# Power.net
KiCad netlist of a schematic drawn in Altium Designer
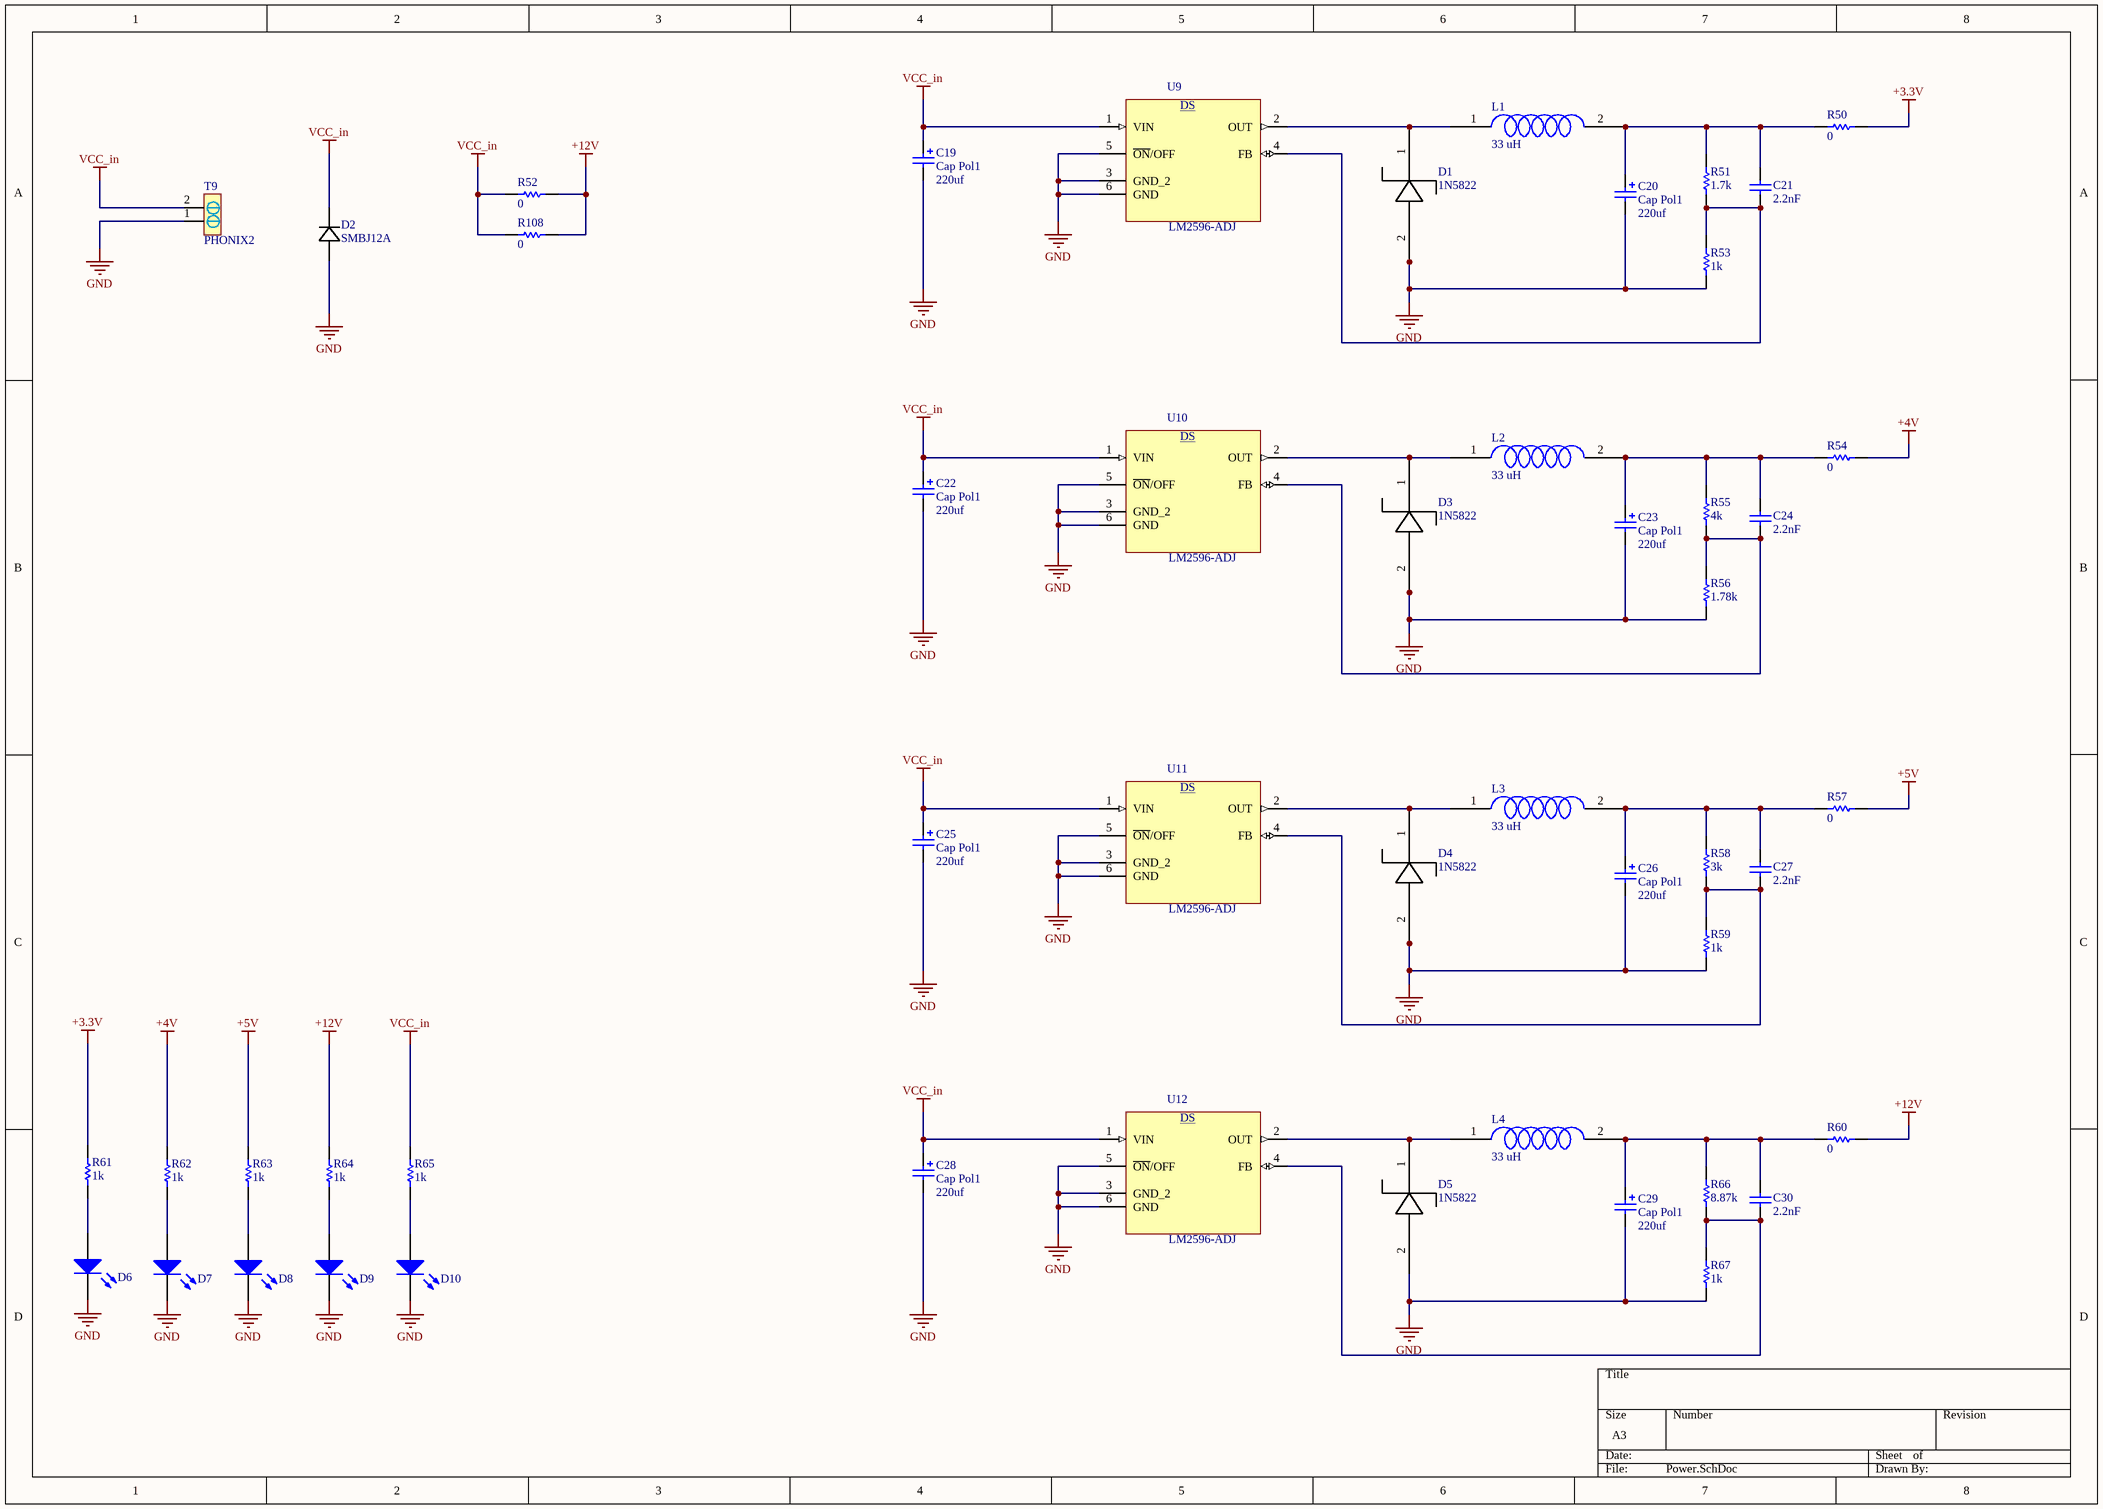
[diagram p0: Power.SchDoc]

(export (version "E")
  (design (tool "Eeschema 10.0.6"))
  (components
    (comp (ref "C19")
      (value "Cap Pol1")
      (footprint "RB5-10.5")
      (description "Polarized Capacitor (Radial)")
      (fields (field (name "ALTIUM_VALUE") "220uf") (field (name "PUBLISHER") "Altium Limited"))
      (libsource (lib "AfraLIB") (part "Cap Pol1"))
    )
    (comp (ref "C20")
      (value "Cap Pol1")
      (footprint "RB5-10.5")
      (description "Polarized Capacitor (Radial)")
      (fields (field (name "ALTIUM_VALUE") "220uf") (field (name "PUBLISHER") "Altium Limited"))
      (libsource (lib "AfraLIB") (part "Cap Pol1"))
    )
    (comp (ref "C21")
      (value "2.2nF")
      (footprint "C-805")
      (description "Capacitor")
      (fields (field (name "Comment") "C-805") (field (name "PUBLISHER") "Altium Limited"))
      (libsource (lib "AfraLIB") (part "C-805"))
    )
    (comp (ref "C22")
      (value "Cap Pol1")
      (footprint "RB5-10.5")
      (description "Polarized Capacitor (Radial)")
      (fields (field (name "ALTIUM_VALUE") "220uf") (field (name "PUBLISHER") "Altium Limited"))
      (libsource (lib "AfraLIB") (part "Cap Pol1"))
    )
    (comp (ref "C23")
      (value "Cap Pol1")
      (footprint "RB5-10.5")
      (description "Polarized Capacitor (Radial)")
      (fields (field (name "ALTIUM_VALUE") "220uf") (field (name "PUBLISHER") "Altium Limited"))
      (libsource (lib "AfraLIB") (part "Cap Pol1"))
    )
    (comp (ref "C24")
      (value "2.2nF")
      (footprint "C-805")
      (description "Capacitor")
      (fields (field (name "Comment") "C-805") (field (name "PUBLISHER") "Altium Limited"))
      (libsource (lib "AfraLIB") (part "C-805"))
    )
    (comp (ref "C25")
      (value "Cap Pol1")
      (footprint "RB5-10.5")
      (description "Polarized Capacitor (Radial)")
      (fields (field (name "ALTIUM_VALUE") "220uf") (field (name "PUBLISHER") "Altium Limited"))
      (libsource (lib "AfraLIB") (part "Cap Pol1"))
    )
    (comp (ref "C26")
      (value "Cap Pol1")
      (footprint "RB5-10.5")
      (description "Polarized Capacitor (Radial)")
      (fields (field (name "ALTIUM_VALUE") "220uf") (field (name "PUBLISHER") "Altium Limited"))
      (libsource (lib "AfraLIB") (part "Cap Pol1"))
    )
    (comp (ref "C27")
      (value "2.2nF")
      (footprint "C-805")
      (description "Capacitor")
      (fields (field (name "Comment") "C-805") (field (name "PUBLISHER") "Altium Limited"))
      (libsource (lib "AfraLIB") (part "C-805"))
    )
    (comp (ref "C28")
      (value "Cap Pol1")
      (footprint "RB5-10.5")
      (description "Polarized Capacitor (Radial)")
      (fields (field (name "ALTIUM_VALUE") "220uf") (field (name "PUBLISHER") "Altium Limited"))
      (libsource (lib "AfraLIB") (part "Cap Pol1"))
    )
    (comp (ref "C29")
      (value "Cap Pol1")
      (footprint "RB5-10.5")
      (description "Polarized Capacitor (Radial)")
      (fields (field (name "ALTIUM_VALUE") "220uf") (field (name "PUBLISHER") "Altium Limited"))
      (libsource (lib "AfraLIB") (part "Cap Pol1"))
    )
    (comp (ref "C30")
      (value "2.2nF")
      (footprint "C-805")
      (description "Capacitor")
      (fields (field (name "Comment") "C-805") (field (name "PUBLISHER") "Altium Limited"))
      (libsource (lib "AfraLIB") (part "C-805"))
    )
    (comp (ref "D1") (value "1N5822") (footprint "1N5822") (libsource (lib "AfraLIB") (part "1N5822")))
    (comp (ref "D2")
      (value "SMBJ12A")
      (footprint "SMB")
      (description "No Description Available")
      (fields
        (field (name "MANUFACTURER_PART_NUMBER") "SMBJ12A-13-F")
        (field (name "COPYRIGHT") "Copyright (C) 2018 Accelerated Designs. All rights reserved")
      )
      (libsource (lib "AfraLIB") (part "SMBJ12A"))
    )
    (comp (ref "D3") (value "1N5822") (footprint "1N5822") (libsource (lib "AfraLIB") (part "1N5822")))
    (comp (ref "D4") (value "1N5822") (footprint "1N5822") (libsource (lib "AfraLIB") (part "1N5822")))
    (comp (ref "D5") (value "1N5822") (footprint "1N5822") (libsource (lib "AfraLIB") (part "1N5822")))
    (comp (ref "D6")
      (value "LED")
      (footprint "LED-805")
      (description "LED Size 805")
      (fields (field (name "PUBLISHER") "Altium Limited"))
      (libsource (lib "AfraLIB") (part "LED-805"))
    )
    (comp (ref "D7")
      (value "LED")
      (footprint "LED-805")
      (description "LED Size 805")
      (fields (field (name "PUBLISHER") "Altium Limited"))
      (libsource (lib "AfraLIB") (part "LED-805"))
    )
    (comp (ref "D8")
      (value "LED")
      (footprint "LED-805")
      (description "LED Size 805")
      (fields (field (name "PUBLISHER") "Altium Limited"))
      (libsource (lib "AfraLIB") (part "LED-805"))
    )
    (comp (ref "D9")
      (value "LED")
      (footprint "LED-805")
      (description "LED Size 805")
      (fields (field (name "PUBLISHER") "Altium Limited"))
      (libsource (lib "AfraLIB") (part "LED-805"))
    )
    (comp (ref "D10")
      (value "LED")
      (footprint "LED-805")
      (description "LED Size 805")
      (fields (field (name "PUBLISHER") "Altium Limited"))
      (libsource (lib "AfraLIB") (part "LED-805"))
    )
    (comp (ref "L1")
      (value "33 uH")
      (footprint "Inductor")
      (description "Power inductor")
      (libsource (lib "AfraLIB") (part "Inductor"))
    )
    (comp (ref "L2")
      (value "33 uH")
      (footprint "Inductor")
      (description "Power inductor")
      (libsource (lib "AfraLIB") (part "Inductor"))
    )
    (comp (ref "L3")
      (value "33 uH")
      (footprint "Inductor")
      (description "Power inductor")
      (libsource (lib "AfraLIB") (part "Inductor"))
    )
    (comp (ref "L4")
      (value "33 uH")
      (footprint "Inductor")
      (description "Power inductor")
      (libsource (lib "AfraLIB") (part "Inductor"))
    )
    (comp (ref "R50")
      (value "0")
      (footprint "R-1206")
      (description "Resistor")
      (fields (field (name "Comment") "R-1206"))
      (libsource (lib "AfraLIB") (part "R-1206"))
    )
    (comp (ref "R51")
      (value "1.7k")
      (footprint "R-805")
      (description "Resistor")
      (fields (field (name "Comment") "R-805"))
      (libsource (lib "AfraLIB") (part "R-805"))
    )
    (comp (ref "R52")
      (value "0")
      (footprint "R-1206")
      (description "Resistor")
      (fields (field (name "Comment") "R-1206"))
      (libsource (lib "AfraLIB") (part "R-1206"))
    )
    (comp (ref "R53")
      (value "1k")
      (footprint "R-805")
      (description "Resistor")
      (fields (field (name "Comment") "R-805"))
      (libsource (lib "AfraLIB") (part "R-805"))
    )
    (comp (ref "R54")
      (value "0")
      (footprint "R-1206")
      (description "Resistor")
      (fields (field (name "Comment") "R-1206"))
      (libsource (lib "AfraLIB") (part "R-1206"))
    )
    (comp (ref "R55")
      (value "4k")
      (footprint "R-805")
      (description "Resistor")
      (fields (field (name "Comment") "R-805"))
      (libsource (lib "AfraLIB") (part "R-805"))
    )
    (comp (ref "R56")
      (value "1.78k")
      (footprint "R-805")
      (description "Resistor")
      (fields (field (name "Comment") "R-805"))
      (libsource (lib "AfraLIB") (part "R-805"))
    )
    (comp (ref "R57")
      (value "0")
      (footprint "R-1206")
      (description "Resistor")
      (fields (field (name "Comment") "R-1206"))
      (libsource (lib "AfraLIB") (part "R-1206"))
    )
    (comp (ref "R58")
      (value "3k")
      (footprint "R-805")
      (description "Resistor")
      (fields (field (name "Comment") "R-805"))
      (libsource (lib "AfraLIB") (part "R-805"))
    )
    (comp (ref "R59")
      (value "1k")
      (footprint "R-805")
      (description "Resistor")
      (fields (field (name "Comment") "R-805"))
      (libsource (lib "AfraLIB") (part "R-805"))
    )
    (comp (ref "R60")
      (value "0")
      (footprint "R-1206")
      (description "Resistor")
      (fields (field (name "Comment") "R-1206"))
      (libsource (lib "AfraLIB") (part "R-1206"))
    )
    (comp (ref "R61")
      (value "1k")
      (footprint "R-805")
      (description "Resistor")
      (fields (field (name "Comment") "R-805"))
      (libsource (lib "AfraLIB") (part "R-805"))
    )
    (comp (ref "R62")
      (value "1k")
      (footprint "R-805")
      (description "Resistor")
      (fields (field (name "Comment") "R-805"))
      (libsource (lib "AfraLIB") (part "R-805"))
    )
    (comp (ref "R63")
      (value "1k")
      (footprint "R-805")
      (description "Resistor")
      (fields (field (name "Comment") "R-805"))
      (libsource (lib "AfraLIB") (part "R-805"))
    )
    (comp (ref "R64")
      (value "1k")
      (footprint "R-805")
      (description "Resistor")
      (fields (field (name "Comment") "R-805"))
      (libsource (lib "AfraLIB") (part "R-805"))
    )
    (comp (ref "R65")
      (value "1k")
      (footprint "R-805")
      (description "Resistor")
      (fields (field (name "Comment") "R-805"))
      (libsource (lib "AfraLIB") (part "R-805"))
    )
    (comp (ref "R66")
      (value "8.87k")
      (footprint "R-805")
      (description "Resistor")
      (fields (field (name "Comment") "R-805"))
      (libsource (lib "AfraLIB") (part "R-805"))
    )
    (comp (ref "R67")
      (value "1k")
      (footprint "R-805")
      (description "Resistor")
      (fields (field (name "Comment") "R-805"))
      (libsource (lib "AfraLIB") (part "R-805"))
    )
    (comp (ref "R108")
      (value "0")
      (footprint "R-1206")
      (description "Resistor")
      (fields (field (name "Comment") "R-1206"))
      (libsource (lib "AfraLIB") (part "R-1206"))
    )
    (comp (ref "T9") (value "PHONIX2") (footprint "PHONIX2") (libsource (lib "AfraLIB") (part "PHONIX2")))
    (comp (ref "U9")
      (value "LM2596-ADJ")
      (footprint "LM2596SX")
      (description "SIMPLE SWITCHER Power Converter 150 KHz 3A Step-Down Voltage Regulator 5-DDPAK/TO-263")
      (fields (field (name "MF") "Texas Instruments"))
      (libsource (lib "AfraLIB") (part "LM2596-ADJ"))
    )
    (comp (ref "U10")
      (value "LM2596-ADJ")
      (footprint "LM2596SX")
      (description "SIMPLE SWITCHER Power Converter 150 KHz 3A Step-Down Voltage Regulator 5-DDPAK/TO-263")
      (fields (field (name "MF") "Texas Instruments"))
      (libsource (lib "AfraLIB") (part "LM2596-ADJ"))
    )
    (comp (ref "U11")
      (value "LM2596-ADJ")
      (footprint "LM2596SX")
      (description "SIMPLE SWITCHER Power Converter 150 KHz 3A Step-Down Voltage Regulator 5-DDPAK/TO-263")
      (fields (field (name "MF") "Texas Instruments"))
      (libsource (lib "AfraLIB") (part "LM2596-ADJ"))
    )
    (comp (ref "U12")
      (value "LM2596-ADJ")
      (footprint "LM2596SX")
      (description "SIMPLE SWITCHER Power Converter 150 KHz 3A Step-Down Voltage Regulator 5-DDPAK/TO-263")
      (fields (field (name "MF") "Texas Instruments"))
      (libsource (lib "AfraLIB") (part "LM2596-ADJ"))
    )
  )
  (nets
    (net (code "1") (name "+3.3V") (class "Default")
      (node (ref "R50") (pin "2") (pinfunction "2_2") (pintype "passive"))
      (node (ref "R61") (pin "2") (pinfunction "2_2") (pintype "passive"))
    )
    (net (code "2") (name "+4V") (class "Default")
      (node (ref "R54") (pin "2") (pinfunction "2_2") (pintype "passive"))
      (node (ref "R62") (pin "2") (pinfunction "2_2") (pintype "passive"))
    )
    (net (code "3") (name "+5V") (class "Default")
      (node (ref "R57") (pin "2") (pinfunction "2_2") (pintype "passive"))
      (node (ref "R63") (pin "2") (pinfunction "2_2") (pintype "passive"))
    )
    (net (code "4") (name "+12V") (class "Default")
      (node (ref "R108") (pin "2") (pinfunction "2_2") (pintype "passive"))
      (node (ref "R52") (pin "2") (pinfunction "2_2") (pintype "passive"))
      (node (ref "R60") (pin "2") (pinfunction "2_2") (pintype "passive"))
      (node (ref "R64") (pin "2") (pinfunction "2_2") (pintype "passive"))
    )
    (net (code "5") (name "GND") (class "Default")
      (node (ref "C19") (pin "2") (pinfunction "2_2") (pintype "passive"))
      (node (ref "C20") (pin "2") (pinfunction "2_2") (pintype "passive"))
      (node (ref "C22") (pin "2") (pinfunction "2_2") (pintype "passive"))
      (node (ref "C23") (pin "2") (pinfunction "2_2") (pintype "passive"))
      (node (ref "C25") (pin "2") (pinfunction "2_2") (pintype "passive"))
      (node (ref "C26") (pin "2") (pinfunction "2_2") (pintype "passive"))
      (node (ref "C28") (pin "2") (pinfunction "2_2") (pintype "passive"))
      (node (ref "C29") (pin "2") (pinfunction "2_2") (pintype "passive"))
      (node (ref "D1") (pin "2") (pintype "passive"))
      (node (ref "D10") (pin "2") (pinfunction "K_2") (pintype "passive"))
      (node (ref "D2") (pin "2") (pinfunction "2_2") (pintype "passive"))
      (node (ref "D3") (pin "2") (pintype "passive"))
      (node (ref "D4") (pin "2") (pintype "passive"))
      (node (ref "D5") (pin "2") (pintype "passive"))
      (node (ref "D6") (pin "2") (pinfunction "K_2") (pintype "passive"))
      (node (ref "D7") (pin "2") (pinfunction "K_2") (pintype "passive"))
      (node (ref "D8") (pin "2") (pinfunction "K_2") (pintype "passive"))
      (node (ref "D9") (pin "2") (pinfunction "K_2") (pintype "passive"))
      (node (ref "R53") (pin "2") (pinfunction "2_2") (pintype "passive"))
      (node (ref "R56") (pin "2") (pinfunction "2_2") (pintype "passive"))
      (node (ref "R59") (pin "2") (pinfunction "2_2") (pintype "passive"))
      (node (ref "R67") (pin "2") (pinfunction "2_2") (pintype "passive"))
      (node (ref "T9") (pin "1") (pintype "passive"))
      (node (ref "U10") (pin "3") (pinfunction "GND_2_3") (pintype "passive"))
      (node (ref "U10") (pin "5") (pinfunction "~{ON}/OFF_5") (pintype "passive"))
      (node (ref "U10") (pin "6") (pinfunction "GND_6") (pintype "passive"))
      (node (ref "U11") (pin "3") (pinfunction "GND_2_3") (pintype "passive"))
      (node (ref "U11") (pin "5") (pinfunction "~{ON}/OFF_5") (pintype "passive"))
      (node (ref "U11") (pin "6") (pinfunction "GND_6") (pintype "passive"))
      (node (ref "U12") (pin "3") (pinfunction "GND_2_3") (pintype "passive"))
      (node (ref "U12") (pin "5") (pinfunction "~{ON}/OFF_5") (pintype "passive"))
      (node (ref "U12") (pin "6") (pinfunction "GND_6") (pintype "passive"))
      (node (ref "U9") (pin "3") (pinfunction "GND_2_3") (pintype "passive"))
      (node (ref "U9") (pin "5") (pinfunction "~{ON}/OFF_5") (pintype "passive"))
      (node (ref "U9") (pin "6") (pinfunction "GND_6") (pintype "passive"))
    )
    (net (code "6") (name "Net-(C20-Pad1)") (class "Default")
      (node (ref "C20") (pin "1") (pinfunction "1_1") (pintype "passive"))
      (node (ref "C21") (pin "2") (pinfunction "2_2") (pintype "passive"))
      (node (ref "L1") (pin "2") (pintype "passive"))
      (node (ref "R50") (pin "1") (pinfunction "1_1") (pintype "passive"))
      (node (ref "R51") (pin "1") (pinfunction "1_1") (pintype "passive"))
    )
    (net (code "7") (name "Net-(C23-Pad1)") (class "Default")
      (node (ref "C23") (pin "1") (pinfunction "1_1") (pintype "passive"))
      (node (ref "C24") (pin "2") (pinfunction "2_2") (pintype "passive"))
      (node (ref "L2") (pin "2") (pintype "passive"))
      (node (ref "R54") (pin "1") (pinfunction "1_1") (pintype "passive"))
      (node (ref "R55") (pin "1") (pinfunction "1_1") (pintype "passive"))
    )
    (net (code "8") (name "Net-(C26-Pad1)") (class "Default")
      (node (ref "C26") (pin "1") (pinfunction "1_1") (pintype "passive"))
      (node (ref "C27") (pin "2") (pinfunction "2_2") (pintype "passive"))
      (node (ref "L3") (pin "2") (pintype "passive"))
      (node (ref "R57") (pin "1") (pinfunction "1_1") (pintype "passive"))
      (node (ref "R58") (pin "1") (pinfunction "1_1") (pintype "passive"))
    )
    (net (code "9") (name "Net-(C29-Pad1)") (class "Default")
      (node (ref "C29") (pin "1") (pinfunction "1_1") (pintype "passive"))
      (node (ref "C30") (pin "2") (pinfunction "2_2") (pintype "passive"))
      (node (ref "L4") (pin "2") (pintype "passive"))
      (node (ref "R60") (pin "1") (pinfunction "1_1") (pintype "passive"))
      (node (ref "R66") (pin "1") (pinfunction "1_1") (pintype "passive"))
    )
    (net (code "10") (name "Net-(D6-A)") (class "Default")
      (node (ref "D6") (pin "1") (pinfunction "A_1") (pintype "passive"))
      (node (ref "R61") (pin "1") (pinfunction "1_1") (pintype "passive"))
    )
    (net (code "11") (name "Net-(D7-A)") (class "Default")
      (node (ref "D7") (pin "1") (pinfunction "A_1") (pintype "passive"))
      (node (ref "R62") (pin "1") (pinfunction "1_1") (pintype "passive"))
    )
    (net (code "12") (name "Net-(D8-A)") (class "Default")
      (node (ref "D8") (pin "1") (pinfunction "A_1") (pintype "passive"))
      (node (ref "R63") (pin "1") (pinfunction "1_1") (pintype "passive"))
    )
    (net (code "13") (name "Net-(D9-A)") (class "Default")
      (node (ref "D9") (pin "1") (pinfunction "A_1") (pintype "passive"))
      (node (ref "R64") (pin "1") (pinfunction "1_1") (pintype "passive"))
    )
    (net (code "14") (name "Net-(D10-A)") (class "Default")
      (node (ref "D10") (pin "1") (pinfunction "A_1") (pintype "passive"))
      (node (ref "R65") (pin "1") (pinfunction "1_1") (pintype "passive"))
    )
    (net (code "15") (name "Net-(U9-FB)") (class "Default")
      (node (ref "C21") (pin "1") (pinfunction "1_1") (pintype "passive"))
      (node (ref "R51") (pin "2") (pinfunction "2_2") (pintype "passive"))
      (node (ref "R53") (pin "1") (pinfunction "1_1") (pintype "passive"))
      (node (ref "U9") (pin "4") (pinfunction "FB_4") (pintype "bidirectional"))
    )
    (net (code "16") (name "Net-(U9-OUT)") (class "Default")
      (node (ref "D1") (pin "1") (pintype "passive"))
      (node (ref "L1") (pin "1") (pintype "passive"))
      (node (ref "U9") (pin "2") (pinfunction "OUT_2") (pintype "output"))
    )
    (net (code "17") (name "Net-(U10-FB)") (class "Default")
      (node (ref "C24") (pin "1") (pinfunction "1_1") (pintype "passive"))
      (node (ref "R55") (pin "2") (pinfunction "2_2") (pintype "passive"))
      (node (ref "R56") (pin "1") (pinfunction "1_1") (pintype "passive"))
      (node (ref "U10") (pin "4") (pinfunction "FB_4") (pintype "bidirectional"))
    )
    (net (code "18") (name "Net-(U10-OUT)") (class "Default")
      (node (ref "D3") (pin "1") (pintype "passive"))
      (node (ref "L2") (pin "1") (pintype "passive"))
      (node (ref "U10") (pin "2") (pinfunction "OUT_2") (pintype "output"))
    )
    (net (code "19") (name "Net-(U11-FB)") (class "Default")
      (node (ref "C27") (pin "1") (pinfunction "1_1") (pintype "passive"))
      (node (ref "R58") (pin "2") (pinfunction "2_2") (pintype "passive"))
      (node (ref "R59") (pin "1") (pinfunction "1_1") (pintype "passive"))
      (node (ref "U11") (pin "4") (pinfunction "FB_4") (pintype "bidirectional"))
    )
    (net (code "20") (name "Net-(U11-OUT)") (class "Default")
      (node (ref "D4") (pin "1") (pintype "passive"))
      (node (ref "L3") (pin "1") (pintype "passive"))
      (node (ref "U11") (pin "2") (pinfunction "OUT_2") (pintype "output"))
    )
    (net (code "21") (name "Net-(U12-FB)") (class "Default")
      (node (ref "C30") (pin "1") (pinfunction "1_1") (pintype "passive"))
      (node (ref "R66") (pin "2") (pinfunction "2_2") (pintype "passive"))
      (node (ref "R67") (pin "1") (pinfunction "1_1") (pintype "passive"))
      (node (ref "U12") (pin "4") (pinfunction "FB_4") (pintype "bidirectional"))
    )
    (net (code "22") (name "Net-(U12-OUT)") (class "Default")
      (node (ref "D5") (pin "1") (pintype "passive"))
      (node (ref "L4") (pin "1") (pintype "passive"))
      (node (ref "U12") (pin "2") (pinfunction "OUT_2") (pintype "output"))
    )
    (net (code "23") (name "VCC_in") (class "Default")
      (node (ref "C19") (pin "1") (pinfunction "1_1") (pintype "passive"))
      (node (ref "C22") (pin "1") (pinfunction "1_1") (pintype "passive"))
      (node (ref "C25") (pin "1") (pinfunction "1_1") (pintype "passive"))
      (node (ref "C28") (pin "1") (pinfunction "1_1") (pintype "passive"))
      (node (ref "D2") (pin "1") (pinfunction "1_1") (pintype "passive"))
      (node (ref "R108") (pin "1") (pinfunction "1_1") (pintype "passive"))
      (node (ref "R52") (pin "1") (pinfunction "1_1") (pintype "passive"))
      (node (ref "R65") (pin "2") (pinfunction "2_2") (pintype "passive"))
      (node (ref "T9") (pin "2") (pintype "passive"))
      (node (ref "U10") (pin "1") (pinfunction "VIN_1") (pintype "input"))
      (node (ref "U11") (pin "1") (pinfunction "VIN_1") (pintype "input"))
      (node (ref "U12") (pin "1") (pinfunction "VIN_1") (pintype "input"))
      (node (ref "U9") (pin "1") (pinfunction "VIN_1") (pintype "input"))
    )
  )
)
